# FMC_ADC_100M_10B_16CHA_TDC.net
KiCad netlist of a schematic drawn in Altium Designer
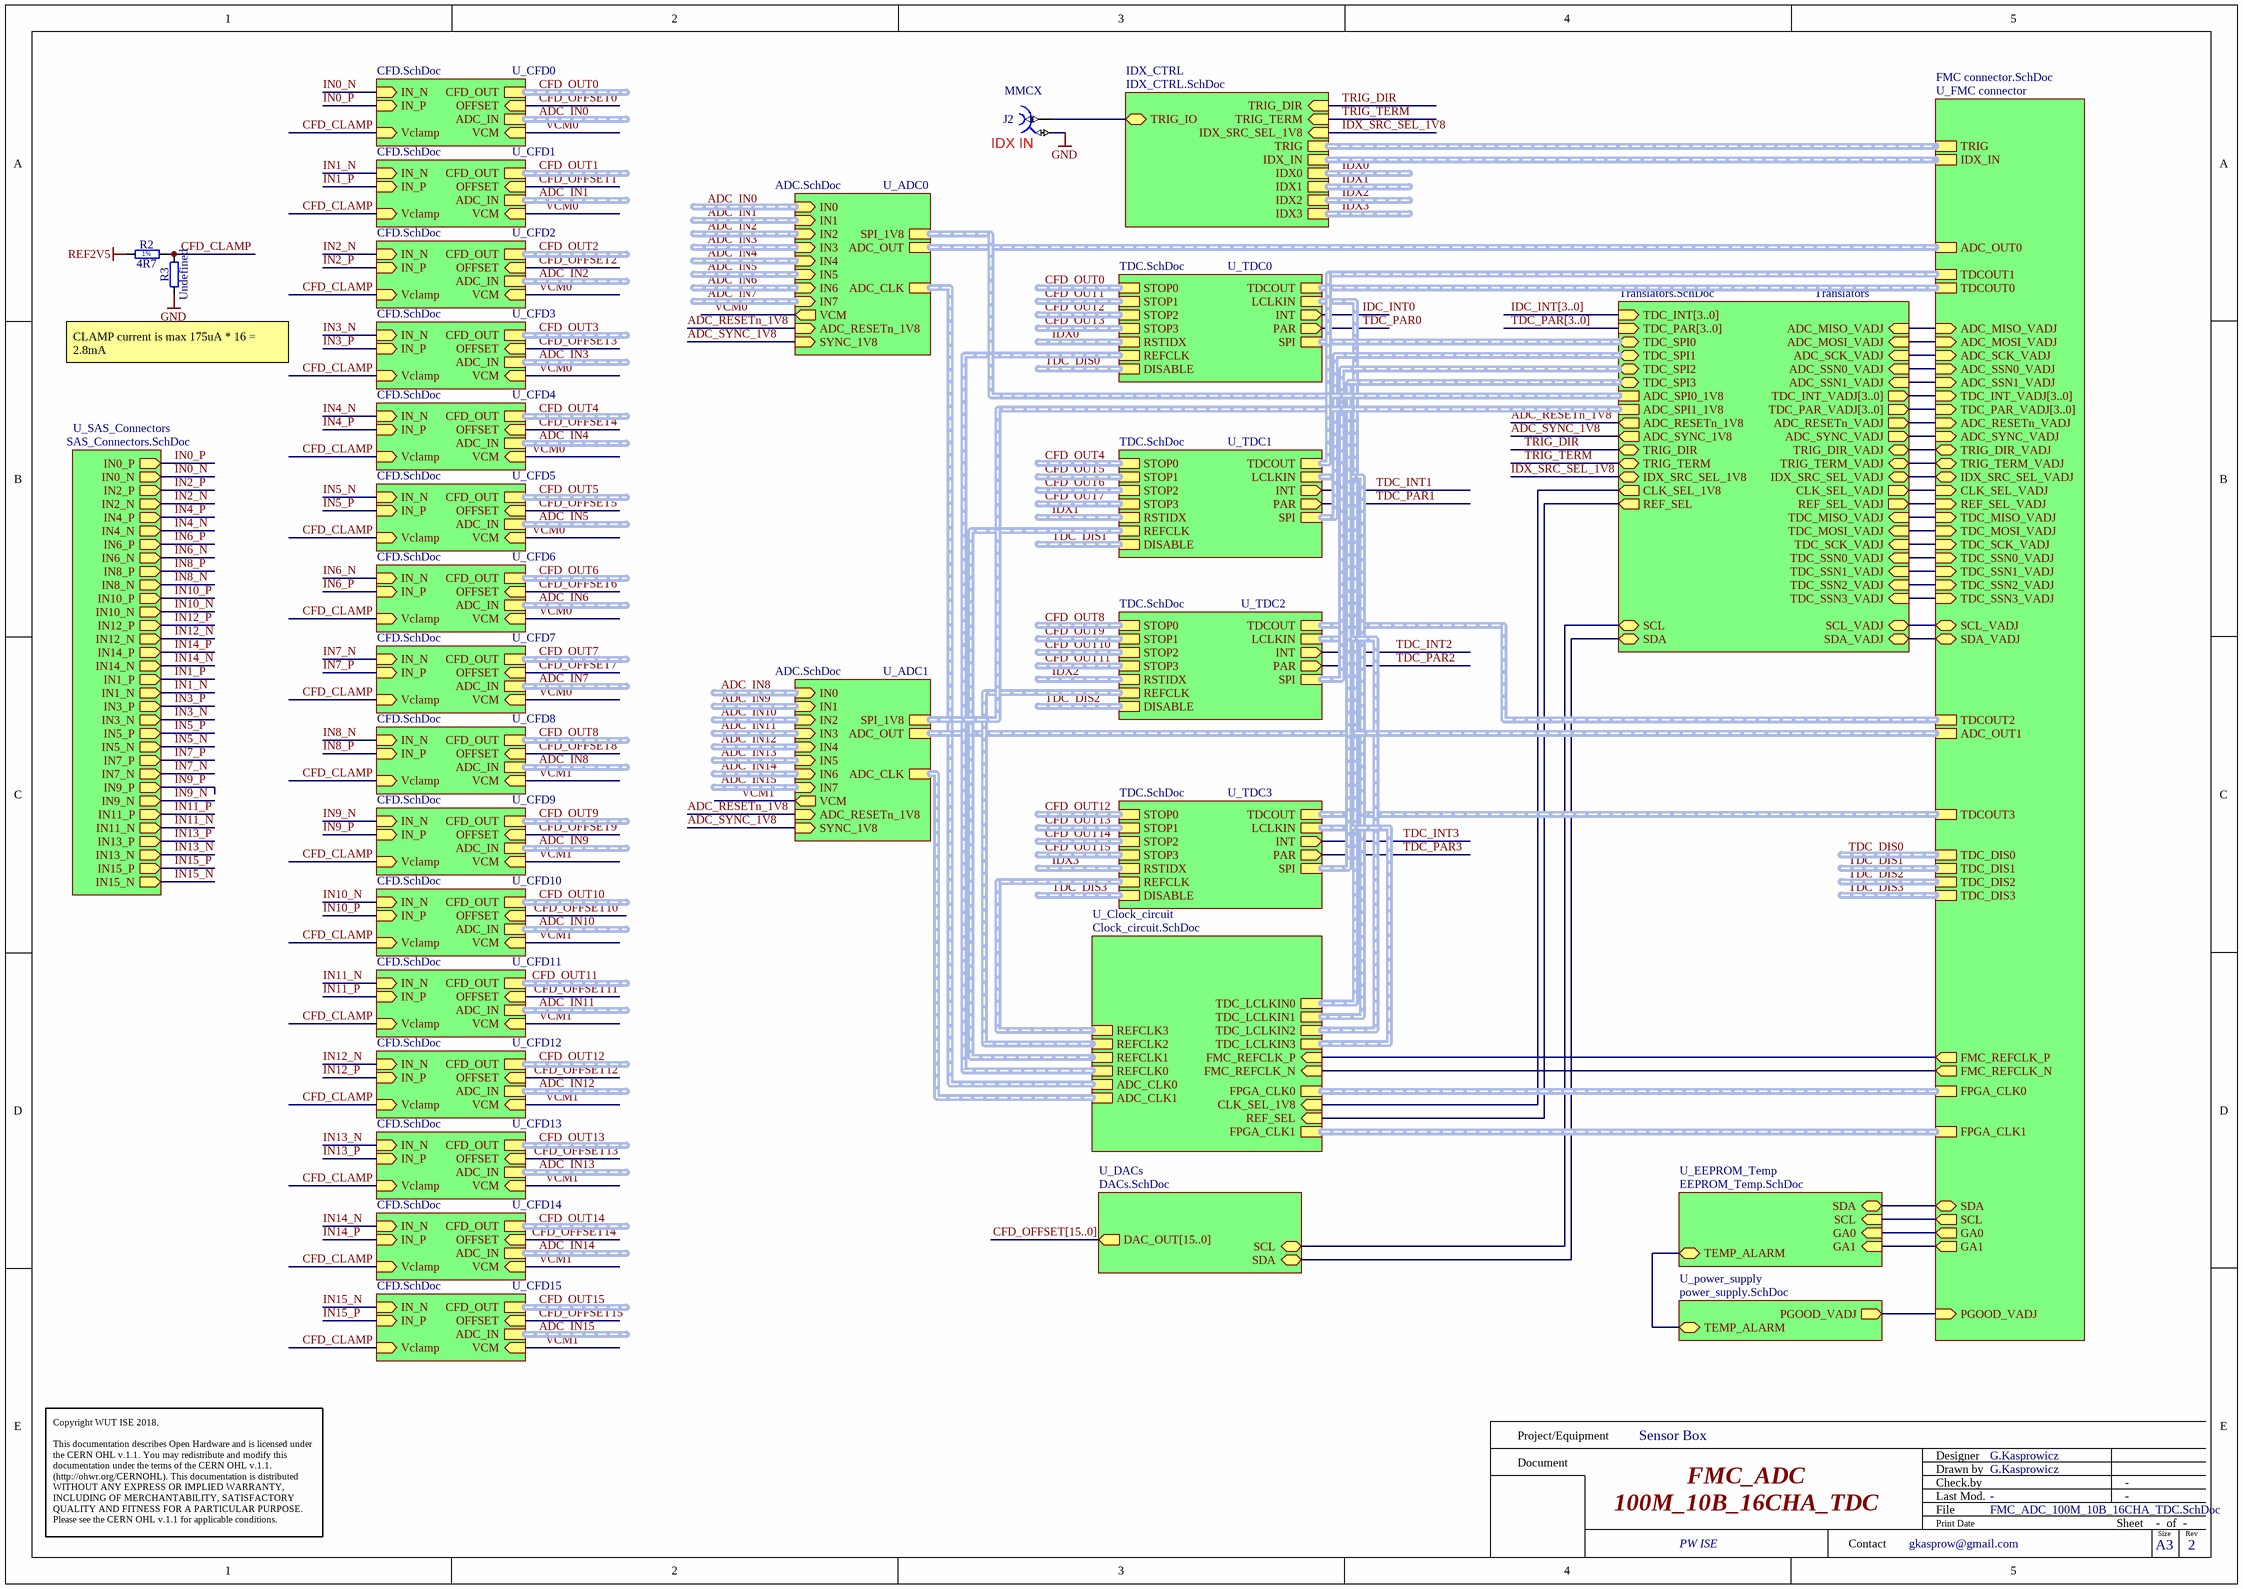
[diagram p0: FMC_ADC_100M_10B_16CHA_TDC.SchDoc]

(export (version "E")
  (design (tool "Eeschema 10.0.6"))
  (components
    (comp (ref "J2")
      (value "Coax_1Female_1Shield")
      (footprint "HUBER-SUHNER_85_MMCX-50-0-1/111 OH")
      (fields
        (field (name "PART NUMBER") "HUBER-SUHNER_85_MMCX-50-0-1/111 OH")
        (field (name "FAMILY") "MMCX")
        (field (name "MANUFACTURER") "HUBER+SUHNER")
        (field (name "MANUFACTURER PART NUMBER") "85_MMCX-50-0-1/111 OH")
        (field (name "AUTHOR") "CERN DEM JLC")
      )
      (libsource (lib "Connectors") (part "Coax_1Female_1Shield"))
    )
    (comp (ref "R2")
      (value "4R7")
      (footprint "RESC1005X40N")
      (description "Resistor - 1%")
      (fields
        (field (name "PART NUMBER") "R0402_4R7_1%_0.0625W_200PPM")
        (field (name "POWER") "0.0625W")
        (field (name "AUTHOR") "CERN DEM JLC")
      )
      (libsource (lib "Resistors") (part "Resistor - 1%"))
    )
    (comp (ref "R3")
      (value "Undefined")
      (footprint "RESC1005X40N")
      (description "Resistor")
      (fields (field (name "PART NUMBER") "R0402_NO-VALUE") (field (name "AUTHOR") "CERN DEM JLC"))
      (libsource (lib "Resistors") (part "Resistor"))
    )
  )
  (nets
    (net (code "59") (name "/CFD_CLAMP") (class "Default")
      (node (ref "R2") (pin "2") (pinfunction "2_2") (pintype "passive"))
      (node (ref "R3") (pin "2") (pinfunction "2_2") (pintype "passive"))
    )
    (net (code "167") (name "/TRIG_IO") (class "Default")
      (node (ref "J2") (pin "1") (pinfunction "1_1") (pintype "bidirectional"))
    )
    (net (code "213") (name "GND") (class "Default")
      (node (ref "J2") (pin "2") (pinfunction "2_2") (pintype "bidirectional"))
      (node (ref "R3") (pin "1") (pinfunction "1_1") (pintype "passive"))
    )
    (net (code "214") (name "REF2V5") (class "Default")
      (node (ref "R2") (pin "1") (pinfunction "1_1") (pintype "passive"))
    )
  )
)
